# openEMSstim_03.net
KiCad netlist of a schematic drawn in EAGLE
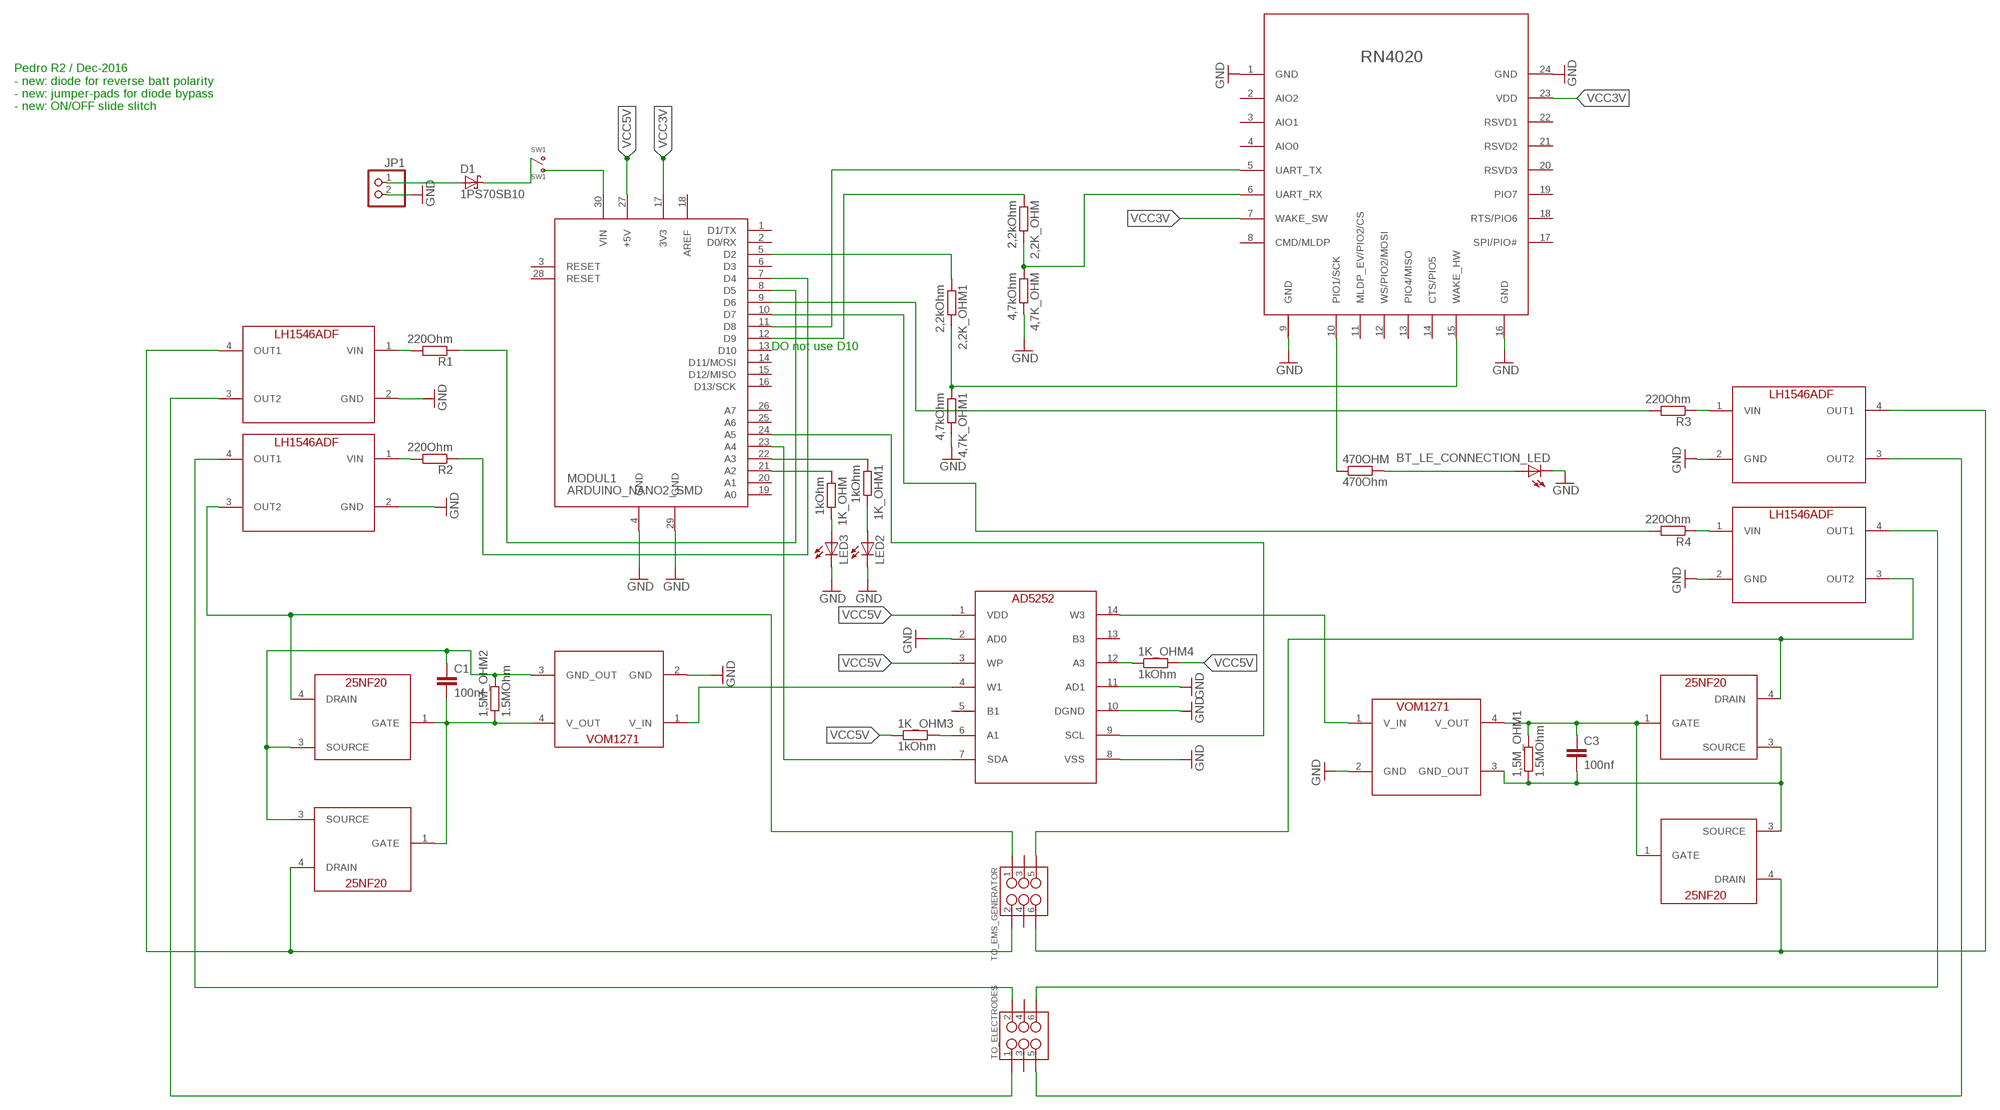
[diagram p0: schematic, sheet 1]

(export (version "E")
  (design (tool "Eeschema 10.0.6"))
  (components
    (comp (ref "1,5M_OHM1")
      (value "1.5MOhm")
      (footprint "eagle-import:R0805")
      (libsource (lib "eagle-import") (part "R-EU_R0805"))
    )
    (comp (ref "1,5M_OHM2")
      (value "1.5MOhm")
      (footprint "eagle-import:R0805")
      (libsource (lib "eagle-import") (part "R-EU_R0805"))
    )
    (comp (ref "1K_OHM")
      (value "1kOhm")
      (footprint "eagle-import:R0805")
      (libsource (lib "eagle-import") (part "R-EU_R0805"))
    )
    (comp (ref "1K_OHM1")
      (value "1kOhm")
      (footprint "eagle-import:R0805")
      (libsource (lib "eagle-import") (part "R-EU_R0805"))
    )
    (comp (ref "1K_OHM3")
      (value "1kOhm")
      (footprint "eagle-import:R0805")
      (libsource (lib "eagle-import") (part "R-EU_R0805"))
    )
    (comp (ref "1K_OHM4")
      (value "1kOhm")
      (footprint "eagle-import:R0805")
      (libsource (lib "eagle-import") (part "R-EU_R0805"))
    )
    (comp (ref "2,2K_OHM")
      (value "2,2kOhm")
      (footprint "eagle-import:R0805")
      (libsource (lib "eagle-import") (part "R-EU_R0805"))
    )
    (comp (ref "2,2K_OHM1")
      (value "2,2kOhm")
      (footprint "eagle-import:R0805")
      (libsource (lib "eagle-import") (part "R-EU_R0805"))
    )
    (comp (ref "4,7K_OHM")
      (value "4,7kOhm")
      (footprint "eagle-import:R0805")
      (libsource (lib "eagle-import") (part "R-EU_R0805"))
    )
    (comp (ref "4,7K_OHM1")
      (value "4,7kOhm")
      (footprint "eagle-import:R0805")
      (libsource (lib "eagle-import") (part "R-EU_R0805"))
    )
    (comp (ref "470OHM")
      (value "470Ohm")
      (footprint "eagle-import:R0805")
      (libsource (lib "eagle-import") (part "R-EU_R0805"))
    )
    (comp (ref "BT_LE_CONNECTION_LED")
      (value "LEDCHIPLED_0603")
      (footprint "eagle-import:CHIPLED_0603")
      (libsource (lib "eagle-import") (part "LEDCHIPLED_0603"))
    )
    (comp (ref "C1")
      (value "100nf")
      (footprint "eagle-import:0805")
      (libsource (lib "eagle-import") (part "CAP0805"))
    )
    (comp (ref "C3")
      (value "100nf")
      (footprint "eagle-import:0805")
      (libsource (lib "eagle-import") (part "CAP0805"))
    )
    (comp (ref "D1")
      (value "1PS70SB10")
      (footprint "eagle-import:SOT323")
      (libsource (lib "eagle-import") (part "1PS70SB10"))
    )
    (comp (ref "JP1")
      (value "PINHD-1X2")
      (footprint "eagle-import:1X02")
      (libsource (lib "eagle-import") (part "PINHD-1X2"))
    )
    (comp (ref "LED2")
      (value "LEDCHIPLED_0603")
      (footprint "eagle-import:CHIPLED_0603")
      (libsource (lib "eagle-import") (part "LEDCHIPLED_0603"))
    )
    (comp (ref "LED3")
      (value "LEDCHIPLED_0603")
      (footprint "eagle-import:CHIPLED_0603")
      (libsource (lib "eagle-import") (part "LEDCHIPLED_0603"))
    )
    (comp (ref "MODUL1")
      (value "ARDUINO_NANO2_SMD")
      (footprint "eagle-import:ARDUINO_NANO2_SMD")
      (libsource (lib "eagle-import") (part "ARDUINO_NANO2_SMD"))
    )
    (comp (ref "MOS01")
      (value "DEV")
      (footprint "eagle-import:PACK")
      (libsource (lib "eagle-import") (part "DEV"))
    )
    (comp (ref "MOS02")
      (value "DEV")
      (footprint "eagle-import:PACK")
      (libsource (lib "eagle-import") (part "DEV"))
    )
    (comp (ref "MOS03")
      (value "DEV")
      (footprint "eagle-import:PACK")
      (libsource (lib "eagle-import") (part "DEV"))
    )
    (comp (ref "MOS04")
      (value "DEV")
      (footprint "eagle-import:PACK")
      (libsource (lib "eagle-import") (part "DEV"))
    )
    (comp (ref "R1")
      (value "220Ohm")
      (footprint "eagle-import:R0805")
      (libsource (lib "eagle-import") (part "R-EU_R0805"))
    )
    (comp (ref "R2")
      (value "220Ohm")
      (footprint "eagle-import:R0805")
      (libsource (lib "eagle-import") (part "R-EU_R0805"))
    )
    (comp (ref "R3")
      (value "220Ohm")
      (footprint "eagle-import:R0805")
      (libsource (lib "eagle-import") (part "R-EU_R0805"))
    )
    (comp (ref "R4")
      (value "220Ohm")
      (footprint "eagle-import:R0805")
      (libsource (lib "eagle-import") (part "R-EU_R0805"))
    )
    (comp (ref "SW1")
      (value "SW1")
      (footprint "eagle-import:SSSS810701")
      (libsource (lib "eagle-import") (part "SSSS810701"))
    )
    (comp (ref "TO_ELECTRODES")
      (value "M03X2")
      (footprint "eagle-import:RIGHT_ANGLED_SHROUED_2X06_6PIN")
      (libsource (lib "eagle-import") (part "M03X2"))
    )
    (comp (ref "TO_EMS_GENERATOR")
      (value "M03X2")
      (footprint "eagle-import:RIGHT_ANGLED_SHROUED_2X06_6PIN")
      (libsource (lib "eagle-import") (part "M03X2"))
    )
    (comp (ref "U$5")
      (value "RN4020")
      (footprint "eagle-import:RN4020")
      (libsource (lib "eagle-import") (part "RN4020"))
    )
    (comp (ref "U$6")
      (value "AD5252")
      (footprint "eagle-import:TSSOP")
      (libsource (lib "eagle-import") (part "AD5252"))
    )
    (comp (ref "U$9")
      (value "VOM1271")
      (footprint "eagle-import:SOP04")
      (libsource (lib "eagle-import") (part "VOM1271"))
    )
    (comp (ref "U$10")
      (value "VOM1271")
      (footprint "eagle-import:SOP04")
      (libsource (lib "eagle-import") (part "VOM1271"))
    )
    (comp (ref "U$11")
      (value "LH1546ADF")
      (footprint "eagle-import:DIP04-SMD")
      (libsource (lib "eagle-import") (part "LH1546ADF"))
    )
    (comp (ref "U$12")
      (value "LH1546ADF")
      (footprint "eagle-import:DIP04-SMD")
      (libsource (lib "eagle-import") (part "LH1546ADF"))
    )
    (comp (ref "U$13")
      (value "LH1546ADF")
      (footprint "eagle-import:DIP04-SMD")
      (libsource (lib "eagle-import") (part "LH1546ADF"))
    )
    (comp (ref "U$14")
      (value "LH1546ADF")
      (footprint "eagle-import:DIP04-SMD")
      (libsource (lib "eagle-import") (part "LH1546ADF"))
    )
  )
  (nets
    (net (code "1") (name "/AREF") (class "Default")
      (node (ref "MODUL1") (pin "18") (pinfunction "AREF_18") (pintype "power_in"))
    )
    (net (code "2") (name "GND") (class "Default")
      (node (ref "4,7K_OHM") (pin "2") (pinfunction "2_2") (pintype "passive"))
      (node (ref "4,7K_OHM1") (pin "2") (pinfunction "2_2") (pintype "passive"))
      (node (ref "BT_LE_CONNECTION_LED") (pin "C") (pinfunction "C_C") (pintype "passive"))
      (node (ref "JP1") (pin "2") (pinfunction "2_2") (pintype "passive"))
      (node (ref "LED2") (pin "C") (pinfunction "C_C") (pintype "passive"))
      (node (ref "LED3") (pin "C") (pinfunction "C_C") (pintype "passive"))
      (node (ref "MODUL1") (pin "29") (pinfunction "GND_29") (pintype "power_in"))
      (node (ref "MODUL1") (pin "4") (pinfunction "GND_4") (pintype "power_in"))
      (node (ref "U$10") (pin "2") (pinfunction "GND_2") (pintype "input"))
      (node (ref "U$11") (pin "2") (pinfunction "GND_2") (pintype "bidirectional"))
      (node (ref "U$12") (pin "2") (pinfunction "GND_2") (pintype "bidirectional"))
      (node (ref "U$13") (pin "2") (pinfunction "GND_2") (pintype "bidirectional"))
      (node (ref "U$14") (pin "2") (pinfunction "GND_2") (pintype "bidirectional"))
      (node (ref "U$5") (pin "1") (pinfunction "GND_1") (pintype "power_in"))
      (node (ref "U$5") (pin "16") (pinfunction "GND_16") (pintype "power_in"))
      (node (ref "U$5") (pin "24") (pinfunction "GND_24") (pintype "power_in"))
      (node (ref "U$5") (pin "9") (pinfunction "GND_9") (pintype "power_in"))
      (node (ref "U$6") (pin "10") (pinfunction "DGND_10") (pintype "bidirectional"))
      (node (ref "U$6") (pin "11") (pinfunction "AD1_11") (pintype "bidirectional"))
      (node (ref "U$6") (pin "2") (pinfunction "AD0_2") (pintype "bidirectional"))
      (node (ref "U$6") (pin "8") (pinfunction "VSS_8") (pintype "bidirectional"))
      (node (ref "U$9") (pin "2") (pinfunction "GND_2") (pintype "input"))
    )
    (net (code "3") (name "Net-(1K_OHM-Pad2)") (class "Default")
      (node (ref "1K_OHM") (pin "2") (pinfunction "2_2") (pintype "passive"))
      (node (ref "LED3") (pin "A") (pinfunction "A_A") (pintype "passive"))
    )
    (net (code "4") (name "Net-(1K_OHM1-Pad2)") (class "Default")
      (node (ref "1K_OHM1") (pin "2") (pinfunction "2_2") (pintype "passive"))
      (node (ref "LED2") (pin "A") (pinfunction "A_A") (pintype "passive"))
    )
    (net (code "5") (name "Net-(470OHM-Pad2)") (class "Default")
      (node (ref "470OHM") (pin "2") (pinfunction "2_2") (pintype "passive"))
      (node (ref "BT_LE_CONNECTION_LED") (pin "A") (pinfunction "A_A") (pintype "passive"))
    )
    (net (code "6") (name "Net-(D1-A)") (class "Default")
      (node (ref "D1") (pin "1") (pinfunction "A_1") (pintype "passive"))
      (node (ref "JP1") (pin "1") (pinfunction "1_1") (pintype "passive"))
    )
    (net (code "7") (name "Net-(D1-K)") (class "Default")
      (node (ref "D1") (pin "3") (pinfunction "K_3") (pintype "passive"))
      (node (ref "SW1") (pin "2") (pinfunction "COM_2") (pintype "bidirectional"))
    )
    (net (code "8") (name "Net-(MODUL1-A2)") (class "Default")
      (node (ref "1K_OHM") (pin "1") (pinfunction "1_1") (pintype "passive"))
      (node (ref "MODUL1") (pin "21") (pinfunction "A2_21") (pintype "bidirectional"))
    )
    (net (code "9") (name "Net-(MODUL1-A3)") (class "Default")
      (node (ref "1K_OHM1") (pin "1") (pinfunction "1_1") (pintype "passive"))
      (node (ref "MODUL1") (pin "22") (pinfunction "A3_22") (pintype "bidirectional"))
    )
    (net (code "10") (name "Net-(MODUL1-A4)") (class "Default")
      (node (ref "MODUL1") (pin "23") (pinfunction "A4_23") (pintype "bidirectional"))
      (node (ref "U$6") (pin "7") (pinfunction "SDA_7") (pintype "bidirectional"))
    )
    (net (code "11") (name "Net-(MODUL1-A5)") (class "Default")
      (node (ref "MODUL1") (pin "24") (pinfunction "A5_24") (pintype "bidirectional"))
      (node (ref "U$6") (pin "9") (pinfunction "SCL_9") (pintype "bidirectional"))
    )
    (net (code "12") (name "Net-(MODUL1-D2)") (class "Default")
      (node (ref "2,2K_OHM1") (pin "1") (pinfunction "1_1") (pintype "passive"))
      (node (ref "MODUL1") (pin "5") (pinfunction "D2_5") (pintype "bidirectional"))
    )
    (net (code "13") (name "Net-(MODUL1-D4)") (class "Default")
      (node (ref "MODUL1") (pin "7") (pinfunction "D4_7") (pintype "bidirectional"))
      (node (ref "R2") (pin "1") (pinfunction "1_1") (pintype "passive"))
    )
    (net (code "14") (name "Net-(MODUL1-D5)") (class "Default")
      (node (ref "MODUL1") (pin "8") (pinfunction "D5_8") (pintype "bidirectional"))
      (node (ref "R1") (pin "1") (pinfunction "1_1") (pintype "passive"))
    )
    (net (code "15") (name "Net-(MODUL1-D6)") (class "Default")
      (node (ref "MODUL1") (pin "9") (pinfunction "D6_9") (pintype "bidirectional"))
      (node (ref "R3") (pin "2") (pinfunction "2_2") (pintype "passive"))
    )
    (net (code "16") (name "Net-(MODUL1-D7)") (class "Default")
      (node (ref "MODUL1") (pin "10") (pinfunction "D7_10") (pintype "bidirectional"))
      (node (ref "R4") (pin "2") (pinfunction "2_2") (pintype "passive"))
    )
    (net (code "17") (name "Net-(MODUL1-D8)") (class "Default")
      (node (ref "MODUL1") (pin "11") (pinfunction "D8_11") (pintype "bidirectional"))
      (node (ref "U$5") (pin "5") (pinfunction "UART_TX_5") (pintype "bidirectional"))
    )
    (net (code "18") (name "Net-(MODUL1-D9)") (class "Default")
      (node (ref "2,2K_OHM") (pin "1") (pinfunction "1_1") (pintype "passive"))
      (node (ref "MODUL1") (pin "12") (pinfunction "D9_12") (pintype "bidirectional"))
    )
    (net (code "19") (name "Net-(MODUL1-VIN)") (class "Default")
      (node (ref "MODUL1") (pin "30") (pinfunction "VIN_30") (pintype "power_in"))
      (node (ref "SW1") (pin "1") (pinfunction "B_1") (pintype "bidirectional"))
    )
    (net (code "20") (name "Net-(MOS01-DRAIN)") (class "Default")
      (node (ref "MOS01") (pin "4") (pinfunction "DRAIN_4") (pintype "bidirectional"))
      (node (ref "TO_EMS_GENERATOR") (pin "1") (pinfunction "1_1") (pintype "bidirectional"))
      (node (ref "U$12") (pin "3") (pinfunction "OUT2_3") (pintype "bidirectional"))
    )
    (net (code "21") (name "Net-(MOS01-GATE)") (class "Default")
      (node (ref "1,5M_OHM2") (pin "1") (pinfunction "1_1") (pintype "passive"))
      (node (ref "C1") (pin "2") (pinfunction "2_2") (pintype "passive"))
      (node (ref "MOS01") (pin "1") (pinfunction "GATE_1") (pintype "input"))
      (node (ref "MOS02") (pin "1") (pinfunction "GATE_1") (pintype "input"))
      (node (ref "U$9") (pin "4") (pinfunction "V_OUT_4") (pintype "output"))
    )
    (net (code "22") (name "Net-(MOS01-SOURCE)") (class "Default")
      (node (ref "1,5M_OHM2") (pin "2") (pinfunction "2_2") (pintype "passive"))
      (node (ref "C1") (pin "1") (pinfunction "1_1") (pintype "passive"))
      (node (ref "MOS01") (pin "3") (pinfunction "SOURCE_3") (pintype "bidirectional"))
      (node (ref "MOS02") (pin "3") (pinfunction "SOURCE_3") (pintype "bidirectional"))
      (node (ref "U$9") (pin "3") (pinfunction "GND_OUT_3") (pintype "output"))
    )
    (net (code "23") (name "Net-(MOS02-DRAIN)") (class "Default")
      (node (ref "MOS02") (pin "4") (pinfunction "DRAIN_4") (pintype "bidirectional"))
      (node (ref "TO_EMS_GENERATOR") (pin "2") (pinfunction "2_2") (pintype "bidirectional"))
      (node (ref "U$11") (pin "4") (pinfunction "OUT1_4") (pintype "bidirectional"))
    )
    (net (code "24") (name "Net-(MOS03-DRAIN)") (class "Default")
      (node (ref "MOS03") (pin "4") (pinfunction "DRAIN_4") (pintype "bidirectional"))
      (node (ref "TO_EMS_GENERATOR") (pin "5") (pinfunction "5_5") (pintype "bidirectional"))
      (node (ref "U$14") (pin "3") (pinfunction "OUT2_3") (pintype "bidirectional"))
    )
    (net (code "25") (name "Net-(MOS03-GATE)") (class "Default")
      (node (ref "1,5M_OHM1") (pin "2") (pinfunction "2_2") (pintype "passive"))
      (node (ref "C3") (pin "1") (pinfunction "1_1") (pintype "passive"))
      (node (ref "MOS03") (pin "1") (pinfunction "GATE_1") (pintype "input"))
      (node (ref "MOS04") (pin "1") (pinfunction "GATE_1") (pintype "input"))
      (node (ref "U$10") (pin "4") (pinfunction "V_OUT_4") (pintype "output"))
    )
    (net (code "26") (name "Net-(MOS03-SOURCE)") (class "Default")
      (node (ref "1,5M_OHM1") (pin "1") (pinfunction "1_1") (pintype "passive"))
      (node (ref "C3") (pin "2") (pinfunction "2_2") (pintype "passive"))
      (node (ref "MOS03") (pin "3") (pinfunction "SOURCE_3") (pintype "bidirectional"))
      (node (ref "MOS04") (pin "3") (pinfunction "SOURCE_3") (pintype "bidirectional"))
      (node (ref "U$10") (pin "3") (pinfunction "GND_OUT_3") (pintype "output"))
    )
    (net (code "27") (name "Net-(MOS04-DRAIN)") (class "Default")
      (node (ref "MOS04") (pin "4") (pinfunction "DRAIN_4") (pintype "bidirectional"))
      (node (ref "TO_EMS_GENERATOR") (pin "6") (pinfunction "6_6") (pintype "bidirectional"))
      (node (ref "U$13") (pin "4") (pinfunction "OUT1_4") (pintype "bidirectional"))
    )
    (net (code "28") (name "Net-(U$5-PIO1{slash}SCK)") (class "Default")
      (node (ref "470OHM") (pin "1") (pinfunction "1_1") (pintype "passive"))
      (node (ref "U$5") (pin "10") (pinfunction "PIO1/SCK_10") (pintype "bidirectional"))
    )
    (net (code "29") (name "Net-(U$5-UART_RX)") (class "Default")
      (node (ref "2,2K_OHM") (pin "2") (pinfunction "2_2") (pintype "passive"))
      (node (ref "4,7K_OHM") (pin "1") (pinfunction "1_1") (pintype "passive"))
      (node (ref "U$5") (pin "6") (pinfunction "UART_RX_6") (pintype "bidirectional"))
    )
    (net (code "30") (name "Net-(U$5-WAKE_HW)") (class "Default")
      (node (ref "2,2K_OHM1") (pin "2") (pinfunction "2_2") (pintype "passive"))
      (node (ref "4,7K_OHM1") (pin "1") (pinfunction "1_1") (pintype "passive"))
      (node (ref "U$5") (pin "15") (pinfunction "WAKE_HW_15") (pintype "bidirectional"))
    )
    (net (code "31") (name "Net-(U$6-A1)") (class "Default")
      (node (ref "1K_OHM3") (pin "2") (pinfunction "2_2") (pintype "passive"))
      (node (ref "U$6") (pin "6") (pinfunction "A1_6") (pintype "bidirectional"))
    )
    (net (code "32") (name "Net-(U$6-A3)") (class "Default")
      (node (ref "1K_OHM4") (pin "1") (pinfunction "1_1") (pintype "passive"))
      (node (ref "U$6") (pin "12") (pinfunction "A3_12") (pintype "bidirectional"))
    )
    (net (code "33") (name "Net-(U$6-W1)") (class "Default")
      (node (ref "U$6") (pin "4") (pinfunction "W1_4") (pintype "bidirectional"))
      (node (ref "U$9") (pin "1") (pinfunction "V_IN_1") (pintype "input"))
    )
    (net (code "34") (name "Net-(U$10-V_IN)") (class "Default")
      (node (ref "U$10") (pin "1") (pinfunction "V_IN_1") (pintype "input"))
      (node (ref "U$6") (pin "14") (pinfunction "W3_14") (pintype "bidirectional"))
    )
    (net (code "35") (name "Net-(U$11-OUT2)") (class "Default")
      (node (ref "TO_ELECTRODES") (pin "1") (pinfunction "1_1") (pintype "bidirectional"))
      (node (ref "U$11") (pin "3") (pinfunction "OUT2_3") (pintype "bidirectional"))
    )
    (net (code "36") (name "Net-(U$11-VIN)") (class "Default")
      (node (ref "R1") (pin "2") (pinfunction "2_2") (pintype "passive"))
      (node (ref "U$11") (pin "1") (pinfunction "VIN_1") (pintype "bidirectional"))
    )
    (net (code "37") (name "Net-(U$12-OUT1)") (class "Default")
      (node (ref "TO_ELECTRODES") (pin "2") (pinfunction "2_2") (pintype "bidirectional"))
      (node (ref "U$12") (pin "4") (pinfunction "OUT1_4") (pintype "bidirectional"))
    )
    (net (code "38") (name "Net-(U$12-VIN)") (class "Default")
      (node (ref "R2") (pin "2") (pinfunction "2_2") (pintype "passive"))
      (node (ref "U$12") (pin "1") (pinfunction "VIN_1") (pintype "bidirectional"))
    )
    (net (code "39") (name "Net-(U$13-OUT2)") (class "Default")
      (node (ref "TO_ELECTRODES") (pin "5") (pinfunction "5_5") (pintype "bidirectional"))
      (node (ref "U$13") (pin "3") (pinfunction "OUT2_3") (pintype "bidirectional"))
    )
    (net (code "40") (name "Net-(U$13-VIN)") (class "Default")
      (node (ref "R3") (pin "1") (pinfunction "1_1") (pintype "passive"))
      (node (ref "U$13") (pin "1") (pinfunction "VIN_1") (pintype "bidirectional"))
    )
    (net (code "41") (name "Net-(U$14-OUT1)") (class "Default")
      (node (ref "TO_ELECTRODES") (pin "6") (pinfunction "6_6") (pintype "bidirectional"))
      (node (ref "U$14") (pin "4") (pinfunction "OUT1_4") (pintype "bidirectional"))
    )
    (net (code "42") (name "Net-(U$14-VIN)") (class "Default")
      (node (ref "R4") (pin "1") (pinfunction "1_1") (pintype "passive"))
      (node (ref "U$14") (pin "1") (pinfunction "VIN_1") (pintype "bidirectional"))
    )
    (net (code "43") (name "VCC3V") (class "Default")
      (node (ref "MODUL1") (pin "17") (pinfunction "3V3_17") (pintype "power_in"))
      (node (ref "U$5") (pin "23") (pinfunction "VDD_23") (pintype "power_in"))
      (node (ref "U$5") (pin "7") (pinfunction "WAKE_SW_7") (pintype "bidirectional"))
    )
    (net (code "44") (name "VCC5V") (class "Default")
      (node (ref "1K_OHM3") (pin "1") (pinfunction "1_1") (pintype "passive"))
      (node (ref "1K_OHM4") (pin "2") (pinfunction "2_2") (pintype "passive"))
      (node (ref "MODUL1") (pin "27") (pinfunction "+5V_27") (pintype "power_in"))
      (node (ref "U$6") (pin "1") (pinfunction "VDD_1") (pintype "bidirectional"))
      (node (ref "U$6") (pin "3") (pinfunction "WP_3") (pintype "bidirectional"))
    )
    (net (code "45") (name "unconnected-(MODUL1-A0-Pad19)") (class "Default")
      (node (ref "MODUL1") (pin "19") (pinfunction "A0_19") (pintype "bidirectional"))
    )
    (net (code "46") (name "unconnected-(MODUL1-A1-Pad20)") (class "Default")
      (node (ref "MODUL1") (pin "20") (pinfunction "A1_20") (pintype "bidirectional"))
    )
    (net (code "47") (name "unconnected-(MODUL1-A6-Pad25)") (class "Default")
      (node (ref "MODUL1") (pin "25") (pinfunction "A6_25") (pintype "bidirectional"))
    )
    (net (code "48") (name "unconnected-(MODUL1-A7-Pad26)") (class "Default")
      (node (ref "MODUL1") (pin "26") (pinfunction "A7_26") (pintype "bidirectional"))
    )
    (net (code "49") (name "unconnected-(MODUL1-D0{slash}RX-Pad2)") (class "Default")
      (node (ref "MODUL1") (pin "2") (pinfunction "D0/RX_2") (pintype "bidirectional"))
    )
    (net (code "50") (name "unconnected-(MODUL1-D1{slash}TX-Pad1)") (class "Default")
      (node (ref "MODUL1") (pin "1") (pinfunction "D1/TX_1") (pintype "bidirectional"))
    )
    (net (code "51") (name "unconnected-(MODUL1-D3-Pad6)") (class "Default")
      (node (ref "MODUL1") (pin "6") (pinfunction "D3_6") (pintype "bidirectional"))
    )
    (net (code "52") (name "unconnected-(MODUL1-D10-Pad13)") (class "Default")
      (node (ref "MODUL1") (pin "13") (pinfunction "D10_13") (pintype "bidirectional"))
    )
    (net (code "53") (name "unconnected-(MODUL1-D11{slash}MOSI-Pad14)") (class "Default")
      (node (ref "MODUL1") (pin "14") (pinfunction "D11/MOSI_14") (pintype "bidirectional"))
    )
    (net (code "54") (name "unconnected-(MODUL1-D12{slash}MISO-Pad15)") (class "Default")
      (node (ref "MODUL1") (pin "15") (pinfunction "D12/MISO_15") (pintype "bidirectional"))
    )
    (net (code "55") (name "unconnected-(MODUL1-D13{slash}SCK-Pad16)") (class "Default")
      (node (ref "MODUL1") (pin "16") (pinfunction "D13/SCK_16") (pintype "bidirectional"))
    )
    (net (code "56") (name "unconnected-(MODUL1-RESET-Pad3)") (class "Default")
      (node (ref "MODUL1") (pin "3") (pinfunction "RESET_3") (pintype "bidirectional"))
    )
    (net (code "57") (name "unconnected-(MODUL1-RESET-Pad28)") (class "Default")
      (node (ref "MODUL1") (pin "28") (pinfunction "RESET_28") (pintype "bidirectional"))
    )
    (net (code "58") (name "unconnected-(SW1-A-Pad3)") (class "Default")
      (node (ref "SW1") (pin "3") (pinfunction "A_3") (pintype "bidirectional"))
    )
    (net (code "59") (name "unconnected-(TO_ELECTRODES-Pad3)") (class "Default")
      (node (ref "TO_ELECTRODES") (pin "3") (pinfunction "3_3") (pintype "bidirectional"))
    )
    (net (code "60") (name "unconnected-(TO_ELECTRODES-Pad4)") (class "Default")
      (node (ref "TO_ELECTRODES") (pin "4") (pinfunction "4_4") (pintype "bidirectional"))
    )
    (net (code "61") (name "unconnected-(TO_EMS_GENERATOR-Pad3)") (class "Default")
      (node (ref "TO_EMS_GENERATOR") (pin "3") (pinfunction "3_3") (pintype "bidirectional"))
    )
    (net (code "62") (name "unconnected-(TO_EMS_GENERATOR-Pad4)") (class "Default")
      (node (ref "TO_EMS_GENERATOR") (pin "4") (pinfunction "4_4") (pintype "bidirectional"))
    )
    (net (code "63") (name "unconnected-(U$5-AIO0-Pad4)") (class "Default")
      (node (ref "U$5") (pin "4") (pinfunction "AIO0_4") (pintype "bidirectional"))
    )
    (net (code "64") (name "unconnected-(U$5-AIO1-Pad3)") (class "Default")
      (node (ref "U$5") (pin "3") (pinfunction "AIO1_3") (pintype "bidirectional"))
    )
    (net (code "65") (name "unconnected-(U$5-AIO2-Pad2)") (class "Default")
      (node (ref "U$5") (pin "2") (pinfunction "AIO2_2") (pintype "bidirectional"))
    )
    (net (code "66") (name "unconnected-(U$5-CMD{slash}MLDP-Pad8)") (class "Default")
      (node (ref "U$5") (pin "8") (pinfunction "CMD/MLDP_8") (pintype "bidirectional"))
    )
    (net (code "67") (name "unconnected-(U$5-CTS{slash}PIO5-Pad14)") (class "Default")
      (node (ref "U$5") (pin "14") (pinfunction "CTS/PIO5_14") (pintype "bidirectional"))
    )
    (net (code "68") (name "unconnected-(U$5-MLDP_EV{slash}PIO2{slash}CS-Pad11)") (class "Default")
      (node (ref "U$5") (pin "11") (pinfunction "MLDP_EV/PIO2/CS_11") (pintype "bidirectional"))
    )
    (net (code "69") (name "unconnected-(U$5-PIO4{slash}MISO-Pad13)") (class "Default")
      (node (ref "U$5") (pin "13") (pinfunction "PIO4/MISO_13") (pintype "bidirectional"))
    )
    (net (code "70") (name "unconnected-(U$5-PIO7-Pad19)") (class "Default")
      (node (ref "U$5") (pin "19") (pinfunction "PIO7_19") (pintype "bidirectional"))
    )
    (net (code "71") (name "unconnected-(U$5-RSVD1-Pad22)") (class "Default")
      (node (ref "U$5") (pin "22") (pinfunction "RSVD1_22") (pintype "bidirectional"))
    )
    (net (code "72") (name "unconnected-(U$5-RSVD2-Pad21)") (class "Default")
      (node (ref "U$5") (pin "21") (pinfunction "RSVD2_21") (pintype "bidirectional"))
    )
    (net (code "73") (name "unconnected-(U$5-RSVD3-Pad20)") (class "Default")
      (node (ref "U$5") (pin "20") (pinfunction "RSVD3_20") (pintype "bidirectional"))
    )
    (net (code "74") (name "unconnected-(U$5-RTS{slash}PIO6-Pad18)") (class "Default")
      (node (ref "U$5") (pin "18") (pinfunction "RTS/PIO6_18") (pintype "bidirectional"))
    )
    (net (code "75") (name "unconnected-(U$5-SPI{slash}PIO#-Pad17)") (class "Default")
      (node (ref "U$5") (pin "17") (pinfunction "SPI/PIO#_17") (pintype "bidirectional"))
    )
    (net (code "76") (name "unconnected-(U$5-WS{slash}PIO2{slash}MOSI-Pad12)") (class "Default")
      (node (ref "U$5") (pin "12") (pinfunction "WS/PIO2/MOSI_12") (pintype "bidirectional"))
    )
    (net (code "77") (name "unconnected-(U$6-B1-Pad5)") (class "Default")
      (node (ref "U$6") (pin "5") (pinfunction "B1_5") (pintype "bidirectional"))
    )
    (net (code "78") (name "unconnected-(U$6-B3-Pad13)") (class "Default")
      (node (ref "U$6") (pin "13") (pinfunction "B3_13") (pintype "bidirectional"))
    )
  )
)
